# MCU.net
KiCad netlist of a schematic drawn in Altium Designer
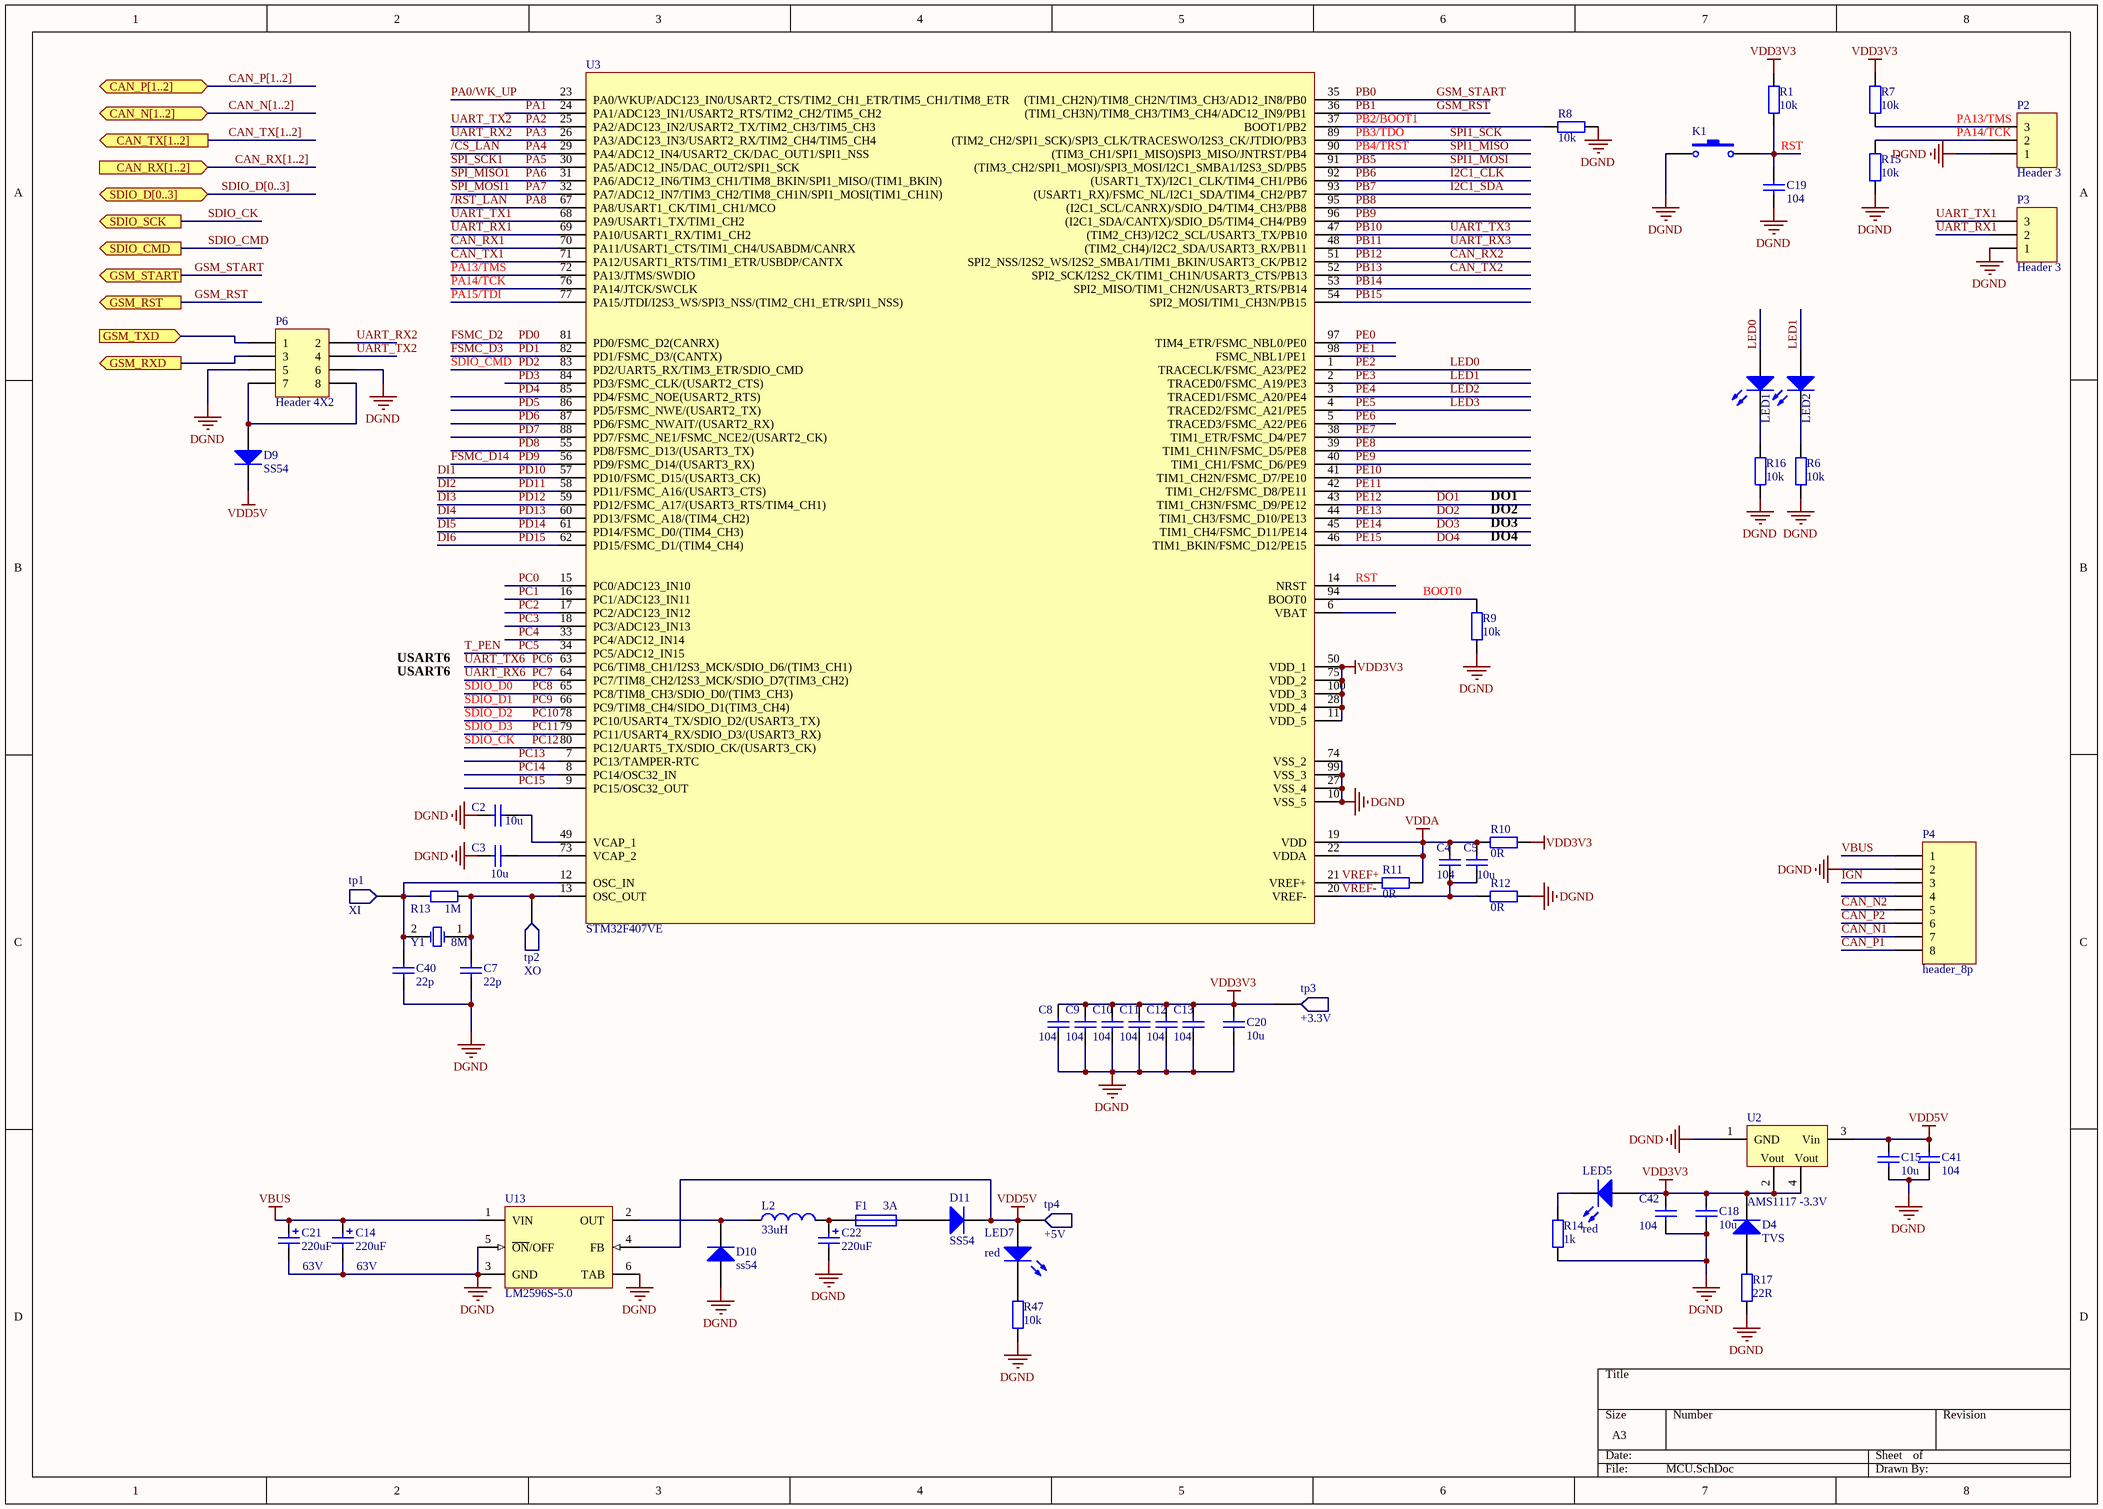
[diagram p0: MCU.SchDoc]

(export (version "E")
  (design (tool "Eeschema 10.0.6"))
  (components
    (comp (ref "C2") (value "10u") (footprint "0603_") (libsource (lib "chxxlib") (part "cap")))
    (comp (ref "C3") (value "10u") (footprint "0603_") (libsource (lib "chxxlib") (part "cap")))
    (comp (ref "C4") (value "104") (footprint "0603_") (libsource (lib "chxxlib") (part "cap")))
    (comp (ref "C5") (value "10u") (footprint "0603_") (libsource (lib "chxxlib") (part "cap")))
    (comp (ref "C7") (value "22p") (footprint "0603_") (libsource (lib "chxxlib") (part "cap")))
    (comp (ref "C8") (value "104") (footprint "0603_") (libsource (lib "chxxlib") (part "cap")))
    (comp (ref "C9") (value "104") (footprint "0603_") (libsource (lib "chxxlib") (part "cap")))
    (comp (ref "C10") (value "104") (footprint "0603_") (libsource (lib "chxxlib") (part "cap")))
    (comp (ref "C11") (value "104") (footprint "0603_") (libsource (lib "chxxlib") (part "cap")))
    (comp (ref "C12") (value "104") (footprint "0603_") (libsource (lib "chxxlib") (part "cap")))
    (comp (ref "C13") (value "104") (footprint "0603_") (libsource (lib "chxxlib") (part "cap")))
    (comp (ref "C14")
      (value "220uF")
      (footprint "Cap - 10mmx10mm")
      (fields (field (name "VDC_") "63V"))
      (libsource (lib "chxxlib") (part "cap-pol"))
    )
    (comp (ref "C15") (value "10u") (footprint "0603_") (libsource (lib "chxxlib") (part "cap")))
    (comp (ref "C18") (value "10u") (footprint "0603_") (libsource (lib "chxxlib") (part "cap")))
    (comp (ref "C19") (value "104") (footprint "0603_") (libsource (lib "chxxlib") (part "cap")))
    (comp (ref "C20") (value "10u") (footprint "0603_") (libsource (lib "chxxlib") (part "cap")))
    (comp (ref "C21")
      (value "220uF")
      (footprint "Cap - 10mmx10mm")
      (fields (field (name "VDC_") "63V"))
      (libsource (lib "chxxlib") (part "cap-pol"))
    )
    (comp (ref "C22")
      (value "220uF")
      (footprint "Cap - 10mmx10mm")
      (libsource (lib "chxxlib") (part "cap-pol"))
    )
    (comp (ref "C40") (value "22p") (footprint "0603_") (libsource (lib "chxxlib") (part "cap")))
    (comp (ref "C41") (value "104") (footprint "0603_") (libsource (lib "chxxlib") (part "cap")))
    (comp (ref "C42") (value "104") (footprint "0603_") (libsource (lib "chxxlib") (part "cap")))
    (comp (ref "D4") (value "TVS") (footprint "SMB") (libsource (lib "chxxlib") (part "diode")))
    (comp (ref "D9") (value "SS54") (footprint "SMA") (libsource (lib "chxxlib") (part "diode")))
    (comp (ref "D10") (value "ss54") (footprint "SMA") (libsource (lib "chxxlib") (part "diode")))
    (comp (ref "D11") (value "SS54") (footprint "SMA") (libsource (lib "chxxlib") (part "diode")))
    (comp (ref "F1") (value "3A") (footprint "3216") (libsource (lib "chxxlib") (part "FUSE")))
    (comp (ref "K1") (value "k") (footprint "key-2pin") (libsource (lib "chxxlib") (part "SW")))
    (comp (ref "L2") (value "33uH") (footprint "Induct 7*7*4") (libsource (lib "chxxlib") (part "inductor")))
    (comp (ref "LED1") (value "red") (footprint "0603_diode") (libsource (lib "") (part "led_1")))
    (comp (ref "LED2") (value "red") (footprint "0603_diode") (libsource (lib "") (part "led_1")))
    (comp (ref "LED5") (value "red") (footprint "0603_diode") (libsource (lib "chxxlib") (part "led")))
    (comp (ref "LED7") (value "red") (footprint "0603_diode") (libsource (lib "chxxlib") (part "led")))
    (comp (ref "P2")
      (value "Header 3")
      (footprint "HDR1X3")
      (description "Header, 3-Pin")
      (fields (field (name "PUBLISHER") "Altium Limited"))
      (libsource (lib "Miscellaneous Connectors") (part "Header 3"))
    )
    (comp (ref "P3")
      (value "Header 3")
      (footprint "HDR1X3")
      (description "Header, 3-Pin")
      (fields (field (name "PUBLISHER") "Altium Limited"))
      (libsource (lib "Miscellaneous Connectors") (part "Header 3"))
    )
    (comp (ref "P4")
      (value "header_8p")
      (footprint "WJ2EDG5.08-8P")
      (description "Pheonix Connector")
      (libsource (lib "powerboardLib") (part "header_8p"))
    )
    (comp (ref "P6")
      (value "Header 4X2")
      (footprint "HDR2X4")
      (description "Header, 4-Pin, Dual row")
      (fields (field (name "PUBLISHER") "Altium Limited"))
      (libsource (lib "Miscellaneous Connectors") (part "Header 4X2"))
    )
    (comp (ref "R1") (value "10k") (footprint "0603_") (libsource (lib "chxxlib") (part "res")))
    (comp (ref "R6") (value "10k") (footprint "0603_") (libsource (lib "chxxlib") (part "res")))
    (comp (ref "R7") (value "10k") (footprint "0603_") (libsource (lib "chxxlib") (part "res")))
    (comp (ref "R8") (value "10k") (footprint "0603_") (libsource (lib "") (part "res_1")))
    (comp (ref "R9") (value "10k") (footprint "0603_") (libsource (lib "chxxlib") (part "res")))
    (comp (ref "R10") (value "0R") (footprint "0603_") (libsource (lib "") (part "res_1")))
    (comp (ref "R11") (value "0R") (footprint "0603_") (libsource (lib "") (part "res_1")))
    (comp (ref "R12") (value "0R") (footprint "0603_") (libsource (lib "") (part "res_1")))
    (comp (ref "R13") (value "1M") (footprint "0603_") (libsource (lib "") (part "res_2")))
    (comp (ref "R14") (value "1k") (footprint "0603_") (libsource (lib "") (part "res_3")))
    (comp (ref "R15") (value "10k") (footprint "0603_") (libsource (lib "chxxlib") (part "res")))
    (comp (ref "R16") (value "10k") (footprint "0603_") (libsource (lib "chxxlib") (part "res")))
    (comp (ref "R17") (value "22R") (footprint "0603_") (libsource (lib "") (part "res_3")))
    (comp (ref "R47") (value "10k") (footprint "0603_") (libsource (lib "chxxlib") (part "res")))
    (comp (ref "tp1") (value "XI") (footprint "testPoint_s") (libsource (lib "chxxlib") (part "pad")))
    (comp (ref "tp2") (value "XO") (footprint "testPoint_s") (libsource (lib "chxxlib") (part "pad")))
    (comp (ref "tp3") (value "+3.3V") (footprint "testPoint") (libsource (lib "chxxlib") (part "pad")))
    (comp (ref "tp4") (value "+5V") (footprint "testPoint") (libsource (lib "chxxlib") (part "pad")))
    (comp (ref "U2")
      (value "AMS1117 -3.3V")
      (footprint "SOT-223")
      (libsource (lib "chxxlib") (part "AMS1117"))
    )
    (comp (ref "U3")
      (value "STM32F407VE")
      (footprint "LQFP100-M")
      (libsource (lib "chxxlib") (part "STM32F407VE"))
    )
    (comp (ref "U13")
      (value "LM2596S-5.0")
      (footprint "TS5B_N")
      (description "SIMPLE SWITCHER Power Converter 150 KHz 3A Step-Down Voltage Regulator")
      (fields
        (field (name "PARTNUMBER") "LM2596S-3.3")
        (field (name "MANUFACTURER") "National Semiconductor")
        (field (name "PUBLISHER") "Altium Limited")
      )
      (libsource (lib "NSC Switcher") (part "LM2596S-3.3"))
    )
    (comp (ref "Y1") (value "8M") (footprint "xtal") (libsource (lib "chxxlib") (part "xtal")))
  )
  (nets
    (net (code "1") (name "/BOOT0") (class "Default")
      (node (ref "R9") (pin "1") (pinfunction "1_1") (pintype "passive"))
      (node (ref "U3") (pin "94") (pinfunction "BOOT0_94") (pintype "passive"))
    )
    (net (code "2") (name "/CAN_N1") (class "Default")
      (node (ref "P4") (pin "7") (pinfunction "7_7") (pintype "passive"))
    )
    (net (code "3") (name "/CAN_N2") (class "Default")
      (node (ref "P4") (pin "5") (pinfunction "5_5") (pintype "passive"))
    )
    (net (code "5") (name "/CAN_P1") (class "Default")
      (node (ref "P4") (pin "8") (pinfunction "8_8") (pintype "passive"))
    )
    (net (code "6") (name "/CAN_P2") (class "Default")
      (node (ref "P4") (pin "6") (pinfunction "6_6") (pintype "passive"))
    )
    (net (code "8") (name "/CAN_RX1") (class "Default")
      (node (ref "U3") (pin "70") (pinfunction "PA11/USART1_CTS/TIM1_CH4/USABDM/CANRX_70") (pintype "passive"))
    )
    (net (code "9") (name "/CAN_RX2") (class "Default")
      (node (ref "U3") (pin "51") (pinfunction "SPI2_NSS/I2S2_WS/I2S2_SMBA1/TIM1_BKIN/USART3_CK/PB12_51") (pintype "passive"))
    )
    (net (code "11") (name "/CAN_TX1") (class "Default")
      (node (ref "U3") (pin "71") (pinfunction "PA12/USART1_RTS/TIM1_ETR/USBDP/CANTX_71") (pintype "passive"))
    )
    (net (code "12") (name "/CAN_TX2") (class "Default")
      (node (ref "U3") (pin "52") (pinfunction "SPI2_SCK/I2S2_CK/TIM1_CH1N/USART3_CTS/PB13_52") (pintype "passive"))
    )
    (net (code "14") (name "/DI1") (class "Default")
      (node (ref "U3") (pin "57") (pinfunction "PD10/FSMC_D15/(USART3_CK)_57") (pintype "passive"))
    )
    (net (code "15") (name "/DI2") (class "Default")
      (node (ref "U3") (pin "58") (pinfunction "PD11/FSMC_A16/(USART3_CTS)_58") (pintype "passive"))
    )
    (net (code "16") (name "/DI3") (class "Default")
      (node (ref "U3") (pin "59") (pinfunction "PD12/FSMC_A17/(USART3_RTS/TIM4_CH1)_59") (pintype "passive"))
    )
    (net (code "17") (name "/DI4") (class "Default")
      (node (ref "U3") (pin "60") (pinfunction "PD13/FSMC_A18/(TIM4_CH2)_60") (pintype "passive"))
    )
    (net (code "18") (name "/DI5") (class "Default")
      (node (ref "U3") (pin "61") (pinfunction "PD14/FSMC_D0/(TIM4_CH3)_61") (pintype "passive"))
    )
    (net (code "19") (name "/DI6") (class "Default")
      (node (ref "U3") (pin "62") (pinfunction "PD15/FSMC_D1/(TIM4_CH4)_62") (pintype "passive"))
    )
    (net (code "20") (name "/DO1") (class "Default")
      (node (ref "U3") (pin "43") (pinfunction "TIM1_CH3N/FSMC_D9/PE12_43") (pintype "passive"))
    )
    (net (code "21") (name "/DO2") (class "Default")
      (node (ref "U3") (pin "44") (pinfunction "TIM1_CH3/FSMC_D10/PE13_44") (pintype "passive"))
    )
    (net (code "22") (name "/DO3") (class "Default")
      (node (ref "U3") (pin "45") (pinfunction "TIM1_CH4/FSMC_D11/PE14_45") (pintype "passive"))
    )
    (net (code "23") (name "/DO4") (class "Default")
      (node (ref "U3") (pin "46") (pinfunction "TIM1_BKIN/FSMC_D12/PE15_46") (pintype "passive"))
    )
    (net (code "24") (name "/FSMC_D2") (class "Default")
      (node (ref "U3") (pin "81") (pinfunction "PD0/FSMC_D2(CANRX)_81") (pintype "passive"))
    )
    (net (code "25") (name "/FSMC_D3") (class "Default")
      (node (ref "U3") (pin "82") (pinfunction "PD1/FSMC_D3/(CANTX)_82") (pintype "passive"))
    )
    (net (code "26") (name "/FSMC_D14") (class "Default")
      (node (ref "U3") (pin "56") (pinfunction "PD9/FSMC_D14/(USART3_RX)_56") (pintype "passive"))
    )
    (net (code "27") (name "/GSM_RST") (class "Default")
      (node (ref "U3") (pin "36") (pinfunction "(TIM1_CH3N)/TIM8_CH3/TIM3_CH4/ADC12_IN9/PB1_36") (pintype "passive"))
    )
    (net (code "28") (name "/GSM_RXD") (class "Default")
      (node (ref "P6") (pin "3") (pinfunction "3_3") (pintype "passive"))
    )
    (net (code "29") (name "/GSM_START") (class "Default")
      (node (ref "U3") (pin "35") (pinfunction "(TIM1_CH2N)/TIM8_CH2N/TIM3_CH3/AD12_IN8/PB0_35") (pintype "passive"))
    )
    (net (code "30") (name "/GSM_TXD") (class "Default")
      (node (ref "P6") (pin "1") (pinfunction "1_1") (pintype "passive"))
    )
    (net (code "31") (name "/I2C1_CLK") (class "Default")
      (node (ref "U3") (pin "92") (pinfunction "(USART1_TX)/I2C1_CLK/TIM4_CH1/PB6_92") (pintype "passive"))
    )
    (net (code "32") (name "/I2C1_SDA") (class "Default")
      (node (ref "U3") (pin "93") (pinfunction "(USART1_RX)/FSMC_NL/I2C1_SDA/TIM4_CH2/PB7_93") (pintype "passive"))
    )
    (net (code "33") (name "/IGN") (class "Default")
      (node (ref "P4") (pin "3") (pinfunction "3_3") (pintype "passive"))
    )
    (net (code "34") (name "/LED0") (class "Default")
      (node (ref "LED1") (pin "1") (pinfunction "A_1") (pintype "passive"))
      (node (ref "U3") (pin "1") (pinfunction "TRACECLK/FSMC_A23/PE2_1") (pintype "passive"))
    )
    (net (code "35") (name "/LED1") (class "Default")
      (node (ref "LED2") (pin "1") (pinfunction "A_1") (pintype "passive"))
      (node (ref "U3") (pin "2") (pinfunction "TRACED0/FSMC_A19/PE3_2") (pintype "passive"))
    )
    (net (code "36") (name "/LED2") (class "Default")
      (node (ref "U3") (pin "3") (pinfunction "TRACED1/FSMC_A20/PE4_3") (pintype "passive"))
    )
    (net (code "37") (name "/LED3") (class "Default")
      (node (ref "U3") (pin "4") (pinfunction "TRACED2/FSMC_A21/PE5_4") (pintype "passive"))
    )
    (net (code "38") (name "/PA0{slash}WK_UP") (class "Default")
      (node (ref "U3") (pin "23") (pinfunction "PA0/WKUP/ADC123_IN0/USART2_CTS/TIM2_CH1_ETR/TIM5_CH1/TIM8_ETR_23") (pintype "passive"))
    )
    (net (code "39") (name "/PA1") (class "Default")
      (node (ref "U3") (pin "24") (pinfunction "PA1/ADC123_IN1/USART2_RTS/TIM2_CH2/TIM5_CH2_24") (pintype "passive"))
    )
    (net (code "40") (name "/PA2") (class "Default")
      (node (ref "P6") (pin "4") (pinfunction "4_4") (pintype "passive"))
      (node (ref "U3") (pin "25") (pinfunction "PA2/ADC123_IN2/USART2_TX/TIM2_CH3/TIM5_CH3_25") (pintype "passive"))
    )
    (net (code "41") (name "/PA3") (class "Default")
      (node (ref "P6") (pin "2") (pinfunction "2_2") (pintype "passive"))
      (node (ref "U3") (pin "26") (pinfunction "PA3/ADC123_IN3/USART2_RX/TIM2_CH4/TIM5_CH4_26") (pintype "passive"))
    )
    (net (code "42") (name "/PA4") (class "Default")
      (node (ref "U3") (pin "29") (pinfunction "PA4/ADC12_IN4/USART2_CK/DAC_OUT1/SPI1_NSS_29") (pintype "passive"))
    )
    (net (code "43") (name "/PA5") (class "Default")
      (node (ref "U3") (pin "30") (pinfunction "PA5/ADC12_IN5/DAC_OUT2/SPI1_SCK_30") (pintype "passive"))
    )
    (net (code "44") (name "/PA6") (class "Default")
      (node (ref "U3") (pin "31") (pinfunction "PA6/ADC12_IN6/TIM3_CH1/TIM8_BKIN/SPI1_MISO/(TIM1_BKIN)_31") (pintype "passive"))
    )
    (net (code "45") (name "/PA7") (class "Default")
      (node (ref "U3") (pin "32") (pinfunction "PA7/ADC12_IN7/TIM3_CH2/TIM8_CH1N/SPI1_MOSI(TIM1_CH1N)_32") (pintype "passive"))
    )
    (net (code "46") (name "/PA8") (class "Default")
      (node (ref "U3") (pin "67") (pinfunction "PA8/USART1_CK/TIM1_CH1/MCO_67") (pintype "passive"))
    )
    (net (code "47") (name "/PA13{slash}TMS") (class "Default")
      (node (ref "P2") (pin "3") (pinfunction "3_3") (pintype "passive"))
      (node (ref "R7") (pin "2") (pinfunction "2_2") (pintype "passive"))
      (node (ref "U3") (pin "72") (pinfunction "PA13/JTMS/SWDIO_72") (pintype "passive"))
    )
    (net (code "48") (name "/PA14{slash}TCK") (class "Default")
      (node (ref "P2") (pin "2") (pinfunction "2_2") (pintype "passive"))
      (node (ref "R15") (pin "1") (pinfunction "1_1") (pintype "passive"))
      (node (ref "U3") (pin "76") (pinfunction "PA14/JTCK/SWCLK_76") (pintype "passive"))
    )
    (net (code "49") (name "/PA15{slash}TDI") (class "Default")
      (node (ref "U3") (pin "77") (pinfunction "PA15/JTDI/I2S3_WS/SPI3_NSS/(TIM2_CH1_ETR/SPI1_NSS)_77") (pintype "passive"))
    )
    (net (code "50") (name "/PB2{slash}BOOT1") (class "Default")
      (node (ref "R8") (pin "1") (pinfunction "1_1") (pintype "passive"))
      (node (ref "U3") (pin "37") (pinfunction "BOOT1/PB2_37") (pintype "passive"))
    )
    (net (code "51") (name "/PB3{slash}TDO") (class "Default")
      (node (ref "U3") (pin "89") (pinfunction "(TIM2_CH2/SPI1_SCK)/SPI3_CLK/TRACESWO/I2S3_CK/JTDIO/PB3_89") (pintype "passive"))
    )
    (net (code "52") (name "/PB4{slash}TRST") (class "Default")
      (node (ref "U3") (pin "90") (pinfunction "(TIM3_CH1/SPI1_MISO)SPI3_MISO/JNTRST/PB4_90") (pintype "passive"))
    )
    (net (code "53") (name "/PB5") (class "Default")
      (node (ref "U3") (pin "91") (pinfunction "(TIM3_CH2/SPI1_MOSI)/SPI3_MOSI/I2C1_SMBA1/I2S3_SD/PB5_91") (pintype "passive"))
    )
    (net (code "54") (name "/PB8") (class "Default")
      (node (ref "U3") (pin "95") (pinfunction "(I2C1_SCL/CANRX)/SDIO_D4/TIM4_CH3/PB8_95") (pintype "passive"))
    )
    (net (code "55") (name "/PB9") (class "Default")
      (node (ref "U3") (pin "96") (pinfunction "(I2C1_SDA/CANTX)/SDIO_D5/TIM4_CH4/PB9_96") (pintype "passive"))
    )
    (net (code "56") (name "/PB10") (class "Default")
      (node (ref "U3") (pin "47") (pinfunction "(TIM2_CH3)/I2C2_SCL/USART3_TX/PB10_47") (pintype "passive"))
    )
    (net (code "57") (name "/PB11") (class "Default")
      (node (ref "U3") (pin "48") (pinfunction "(TIM2_CH4)/I2C2_SDA/USART3_RX/PB11_48") (pintype "passive"))
    )
    (net (code "58") (name "/PB14") (class "Default")
      (node (ref "U3") (pin "53") (pinfunction "SPI2_MISO/TIM1_CH2N/USART3_RTS/PB14_53") (pintype "passive"))
    )
    (net (code "59") (name "/PB15") (class "Default")
      (node (ref "U3") (pin "54") (pinfunction "SPI2_MOSI/TIM1_CH3N/PB15_54") (pintype "passive"))
    )
    (net (code "60") (name "/PC0") (class "Default")
      (node (ref "U3") (pin "15") (pinfunction "PC0/ADC123_IN10_15") (pintype "passive"))
    )
    (net (code "61") (name "/PC1") (class "Default")
      (node (ref "U3") (pin "16") (pinfunction "PC1/ADC123_IN11_16") (pintype "passive"))
    )
    (net (code "62") (name "/PC2") (class "Default")
      (node (ref "U3") (pin "17") (pinfunction "PC2/ADC123_IN12_17") (pintype "passive"))
    )
    (net (code "63") (name "/PC3") (class "Default")
      (node (ref "U3") (pin "18") (pinfunction "PC3/ADC123_IN13_18") (pintype "passive"))
    )
    (net (code "64") (name "/PC4") (class "Default")
      (node (ref "U3") (pin "33") (pinfunction "PC4/ADC12_IN14_33") (pintype "passive"))
    )
    (net (code "65") (name "/PC5") (class "Default")
      (node (ref "U3") (pin "34") (pinfunction "PC5/ADC12_IN15_34") (pintype "passive"))
    )
    (net (code "66") (name "/PC6") (class "Default")
      (node (ref "U3") (pin "63") (pinfunction "PC6/TIM8_CH1/I2S3_MCK/SDIO_D6/(TIM3_CH1)_63") (pintype "passive"))
    )
    (net (code "67") (name "/PC7") (class "Default")
      (node (ref "U3") (pin "64") (pinfunction "PC7/TIM8_CH2/I2S3_MCK/SDIO_D7(TIM3_CH2)_64") (pintype "passive"))
    )
    (net (code "68") (name "/PC12") (class "Default")
      (node (ref "U3") (pin "80") (pinfunction "PC12/UART5_TX/SDIO_CK/(USART3_CK)_80") (pintype "passive"))
    )
    (net (code "69") (name "/PC13") (class "Default")
      (node (ref "U3") (pin "7") (pinfunction "PC13/TAMPER-RTC_7") (pintype "passive"))
    )
    (net (code "70") (name "/PC14") (class "Default")
      (node (ref "U3") (pin "8") (pinfunction "PC14/OSC32_IN_8") (pintype "passive"))
    )
    (net (code "71") (name "/PC15") (class "Default")
      (node (ref "U3") (pin "9") (pinfunction "PC15/OSC32_OUT_9") (pintype "passive"))
    )
    (net (code "72") (name "/PD2") (class "Default")
      (node (ref "U3") (pin "83") (pinfunction "PD2/UART5_RX/TIM3_ETR/SDIO_CMD_83") (pintype "passive"))
    )
    (net (code "73") (name "/PD3") (class "Default")
      (node (ref "U3") (pin "84") (pinfunction "PD3/FSMC_CLK/(USART2_CTS)_84") (pintype "passive"))
    )
    (net (code "74") (name "/PD4") (class "Default")
      (node (ref "U3") (pin "85") (pinfunction "PD4/FSMC_NOE(USART2_RTS)_85") (pintype "passive"))
    )
    (net (code "75") (name "/PD5") (class "Default")
      (node (ref "U3") (pin "86") (pinfunction "PD5/FSMC_NWE/(USART2_TX)_86") (pintype "passive"))
    )
    (net (code "76") (name "/PD6") (class "Default")
      (node (ref "U3") (pin "87") (pinfunction "PD6/FSMC_NWAIT/(USART2_RX)_87") (pintype "passive"))
    )
    (net (code "77") (name "/PD7") (class "Default")
      (node (ref "U3") (pin "88") (pinfunction "PD7/FSMC_NE1/FSMC_NCE2/(USART2_CK)_88") (pintype "passive"))
    )
    (net (code "78") (name "/PD8") (class "Default")
      (node (ref "U3") (pin "55") (pinfunction "PD8/FSMC_D13/(USART3_TX)_55") (pintype "passive"))
    )
    (net (code "79") (name "/PE0") (class "Default")
      (node (ref "U3") (pin "97") (pinfunction "TIM4_ETR/FSMC_NBL0/PE0_97") (pintype "passive"))
    )
    (net (code "80") (name "/PE1") (class "Default")
      (node (ref "U3") (pin "98") (pinfunction "FSMC_NBL1/PE1_98") (pintype "passive"))
    )
    (net (code "81") (name "/PE6") (class "Default")
      (node (ref "U3") (pin "5") (pinfunction "TRACED3/FSMC_A22/PE6_5") (pintype "passive"))
    )
    (net (code "82") (name "/PE7") (class "Default")
      (node (ref "U3") (pin "38") (pinfunction "TIM1_ETR/FSMC_D4/PE7_38") (pintype "passive"))
    )
    (net (code "83") (name "/PE8") (class "Default")
      (node (ref "U3") (pin "39") (pinfunction "TIM1_CH1N/FSMC_D5/PE8_39") (pintype "passive"))
    )
    (net (code "84") (name "/PE9") (class "Default")
      (node (ref "U3") (pin "40") (pinfunction "TIM1_CH1/FSMC_D6/PE9_40") (pintype "passive"))
    )
    (net (code "85") (name "/PE10") (class "Default")
      (node (ref "U3") (pin "41") (pinfunction "TIM1_CH2N/FSMC_D7/PE10_41") (pintype "passive"))
    )
    (net (code "86") (name "/PE11") (class "Default")
      (node (ref "U3") (pin "42") (pinfunction "TIM1_CH2/FSMC_D8/PE11_42") (pintype "passive"))
    )
    (net (code "87") (name "/RST") (class "Default")
      (node (ref "C19") (pin "1") (pinfunction "1_1") (pintype "passive"))
      (node (ref "K1") (pin "2") (pinfunction "2_2") (pintype "passive"))
      (node (ref "R1") (pin "2") (pinfunction "2_2") (pintype "passive"))
      (node (ref "U3") (pin "14") (pinfunction "NRST_14") (pintype "passive"))
    )
    (net (code "88") (name "/SDIO_D0") (class "Default")
      (node (ref "U3") (pin "65") (pinfunction "PC8/TIM8_CH3/SDIO_D0/(TIM3_CH3)_65") (pintype "passive"))
    )
    (net (code "89") (name "/SDIO_D1") (class "Default")
      (node (ref "U3") (pin "66") (pinfunction "PC9/TIM8_CH4/SIDO_D1(TIM3_CH4)_66") (pintype "passive"))
    )
    (net (code "90") (name "/SDIO_D2") (class "Default")
      (node (ref "U3") (pin "78") (pinfunction "PC10/USART4_TX/SDIO_D2/(USART3_TX)_78") (pintype "passive"))
    )
    (net (code "91") (name "/SDIO_D3") (class "Default")
      (node (ref "U3") (pin "79") (pinfunction "PC11/USART4_RX/SDIO_D3/(USART3_RX)_79") (pintype "passive"))
    )
    (net (code "93") (name "/UART_RX1") (class "Default")
      (node (ref "P3") (pin "2") (pinfunction "2_2") (pintype "passive"))
      (node (ref "U3") (pin "69") (pinfunction "PA10/USART1_RX/TIM1_CH2_69") (pintype "passive"))
    )
    (net (code "94") (name "/UART_TX1") (class "Default")
      (node (ref "P3") (pin "3") (pinfunction "3_3") (pintype "passive"))
      (node (ref "U3") (pin "68") (pinfunction "PA9/USART1_TX/TIM1_CH2_68") (pintype "passive"))
    )
    (net (code "95") (name "/VREF+") (class "Default")
      (node (ref "R11") (pin "1") (pinfunction "1_1") (pintype "passive"))
      (node (ref "U3") (pin "21") (pinfunction "VREF+_21") (pintype "passive"))
    )
    (net (code "96") (name "/VREF-") (class "Default")
      (node (ref "C4") (pin "2") (pinfunction "2_2") (pintype "passive"))
      (node (ref "C5") (pin "2") (pinfunction "2_2") (pintype "passive"))
      (node (ref "R12") (pin "1") (pinfunction "1_1") (pintype "passive"))
      (node (ref "U3") (pin "20") (pinfunction "VREF-_20") (pintype "passive"))
    )
    (net (code "97") (name "DGND") (class "Default")
      (node (ref "C10") (pin "2") (pinfunction "2_2") (pintype "passive"))
      (node (ref "C11") (pin "2") (pinfunction "2_2") (pintype "passive"))
      (node (ref "C12") (pin "2") (pinfunction "2_2") (pintype "passive"))
      (node (ref "C13") (pin "2") (pinfunction "2_2") (pintype "passive"))
      (node (ref "C14") (pin "2") (pinfunction "2_2") (pintype "passive"))
      (node (ref "C15") (pin "1") (pinfunction "1_1") (pintype "passive"))
      (node (ref "C18") (pin "1") (pinfunction "1_1") (pintype "passive"))
      (node (ref "C19") (pin "2") (pinfunction "2_2") (pintype "passive"))
      (node (ref "C2") (pin "1") (pinfunction "1_1") (pintype "passive"))
      (node (ref "C20") (pin "1") (pinfunction "1_1") (pintype "passive"))
      (node (ref "C21") (pin "2") (pinfunction "2_2") (pintype "passive"))
      (node (ref "C22") (pin "2") (pinfunction "2_2") (pintype "passive"))
      (node (ref "C3") (pin "1") (pinfunction "1_1") (pintype "passive"))
      (node (ref "C40") (pin "1") (pinfunction "1_1") (pintype "passive"))
      (node (ref "C41") (pin "2") (pinfunction "2_2") (pintype "passive"))
      (node (ref "C42") (pin "2") (pinfunction "2_2") (pintype "passive"))
      (node (ref "C7") (pin "1") (pinfunction "1_1") (pintype "passive"))
      (node (ref "C8") (pin "2") (pinfunction "2_2") (pintype "passive"))
      (node (ref "C9") (pin "2") (pinfunction "2_2") (pintype "passive"))
      (node (ref "D10") (pin "A") (pinfunction "A_A") (pintype "passive"))
      (node (ref "K1") (pin "1") (pinfunction "1_1") (pintype "passive"))
      (node (ref "P2") (pin "1") (pinfunction "1_1") (pintype "passive"))
      (node (ref "P3") (pin "1") (pinfunction "1_1") (pintype "passive"))
      (node (ref "P4") (pin "2") (pinfunction "2_2") (pintype "passive"))
      (node (ref "P6") (pin "5") (pinfunction "5_5") (pintype "passive"))
      (node (ref "P6") (pin "6") (pinfunction "6_6") (pintype "passive"))
      (node (ref "R12") (pin "2") (pinfunction "2_2") (pintype "passive"))
      (node (ref "R14") (pin "1") (pinfunction "1_1") (pintype "passive"))
      (node (ref "R15") (pin "2") (pinfunction "2_2") (pintype "passive"))
      (node (ref "R16") (pin "2") (pinfunction "2_2") (pintype "passive"))
      (node (ref "R17") (pin "1") (pinfunction "1_1") (pintype "passive"))
      (node (ref "R47") (pin "2") (pinfunction "2_2") (pintype "passive"))
      (node (ref "R6") (pin "2") (pinfunction "2_2") (pintype "passive"))
      (node (ref "R8") (pin "2") (pinfunction "2_2") (pintype "passive"))
      (node (ref "R9") (pin "2") (pinfunction "2_2") (pintype "passive"))
      (node (ref "U13") (pin "3") (pinfunction "GND_3") (pintype "power_in"))
      (node (ref "U13") (pin "5") (pinfunction "~{ON}/OFF_5") (pintype "input"))
      (node (ref "U13") (pin "6") (pinfunction "TAB_6") (pintype "power_in"))
      (node (ref "U2") (pin "1") (pinfunction "GND_1") (pintype "passive"))
      (node (ref "U3") (pin "10") (pinfunction "VSS_5_10") (pintype "passive"))
      (node (ref "U3") (pin "27") (pinfunction "VSS_4_27") (pintype "passive"))
      (node (ref "U3") (pin "74") (pinfunction "VSS_2_74") (pintype "passive"))
      (node (ref "U3") (pin "99") (pinfunction "VSS_3_99") (pintype "passive"))
    )
    (net (code "98") (name "Net-(C22-Pad1)") (class "Default")
      (node (ref "C22") (pin "1") (pinfunction "1_1") (pintype "passive"))
      (node (ref "F1") (pin "1") (pinfunction "1_1") (pintype "passive"))
      (node (ref "L2") (pin "2") (pinfunction "2_2") (pintype "passive"))
    )
    (net (code "99") (name "Net-(D4-PadA)") (class "Default")
      (node (ref "D4") (pin "A") (pinfunction "A_A") (pintype "passive"))
      (node (ref "R17") (pin "2") (pinfunction "2_2") (pintype "passive"))
    )
    (net (code "100") (name "Net-(D9-PadA)") (class "Default")
      (node (ref "D9") (pin "A") (pinfunction "A_A") (pintype "passive"))
      (node (ref "P6") (pin "7") (pinfunction "7_7") (pintype "passive"))
      (node (ref "P6") (pin "8") (pinfunction "8_8") (pintype "passive"))
    )
    (net (code "101") (name "Net-(D11-PadA)") (class "Default")
      (node (ref "D11") (pin "A") (pinfunction "A_A") (pintype "passive"))
      (node (ref "F1") (pin "2") (pinfunction "2_2") (pintype "passive"))
    )
    (net (code "102") (name "Net-(LED1-K)") (class "Default")
      (node (ref "LED1") (pin "2") (pinfunction "K_2") (pintype "passive"))
      (node (ref "R16") (pin "1") (pinfunction "1_1") (pintype "passive"))
    )
    (net (code "103") (name "Net-(LED2-K)") (class "Default")
      (node (ref "LED2") (pin "2") (pinfunction "K_2") (pintype "passive"))
      (node (ref "R6") (pin "1") (pinfunction "1_1") (pintype "passive"))
    )
    (net (code "104") (name "Net-(LED5-K)") (class "Default")
      (node (ref "LED5") (pin "2") (pinfunction "K_2") (pintype "passive"))
      (node (ref "R14") (pin "2") (pinfunction "2_2") (pintype "passive"))
    )
    (net (code "105") (name "Net-(LED7-K)") (class "Default")
      (node (ref "LED7") (pin "2") (pinfunction "K_2") (pintype "passive"))
      (node (ref "R47") (pin "1") (pinfunction "1_1") (pintype "passive"))
    )
    (net (code "106") (name "Net-(U3-OSC_IN)") (class "Default")
      (node (ref "C40") (pin "2") (pinfunction "2_2") (pintype "passive"))
      (node (ref "R13") (pin "2") (pinfunction "2_2") (pintype "passive"))
      (node (ref "U3") (pin "12") (pinfunction "OSC_IN_12") (pintype "passive"))
      (node (ref "Y1") (pin "2") (pinfunction "OSC2_2") (pintype "passive"))
      (node (ref "tp1") (pin "1") (pinfunction "1_1") (pintype "power_in"))
    )
    (net (code "107") (name "Net-(U3-OSC_OUT)") (class "Default")
      (node (ref "C7") (pin "2") (pinfunction "2_2") (pintype "passive"))
      (node (ref "R13") (pin "1") (pinfunction "1_1") (pintype "passive"))
      (node (ref "U3") (pin "13") (pinfunction "OSC_OUT_13") (pintype "passive"))
      (node (ref "Y1") (pin "1") (pinfunction "OSC1_1") (pintype "passive"))
      (node (ref "tp2") (pin "1") (pinfunction "1_1") (pintype "power_in"))
    )
    (net (code "108") (name "Net-(U3-VCAP_1)") (class "Default")
      (node (ref "C2") (pin "2") (pinfunction "2_2") (pintype "passive"))
      (node (ref "U3") (pin "49") (pinfunction "VCAP_1_49") (pintype "passive"))
    )
    (net (code "109") (name "Net-(U3-VCAP_2)") (class "Default")
      (node (ref "C3") (pin "2") (pinfunction "2_2") (pintype "passive"))
      (node (ref "U3") (pin "73") (pinfunction "VCAP_2_73") (pintype "passive"))
    )
    (net (code "110") (name "Net-(U13-OUT)") (class "Default")
      (node (ref "D10") (pin "K") (pinfunction "K_K") (pintype "passive"))
      (node (ref "L2") (pin "1") (pinfunction "1_1") (pintype "passive"))
      (node (ref "U13") (pin "2") (pinfunction "OUT_2") (pintype "power_in"))
    )
    (net (code "111") (name "VBUS") (class "Default")
      (node (ref "C14") (pin "1") (pinfunction "1_1") (pintype "passive"))
      (node (ref "C21") (pin "1") (pinfunction "1_1") (pintype "passive"))
      (node (ref "P4") (pin "1") (pinfunction "1_1") (pintype "passive"))
      (node (ref "U13") (pin "1") (pinfunction "VIN_1") (pintype "power_in"))
    )
    (net (code "112") (name "VDD3V3") (class "Default")
      (node (ref "C10") (pin "1") (pinfunction "1_1") (pintype "passive"))
      (node (ref "C11") (pin "1") (pinfunction "1_1") (pintype "passive"))
      (node (ref "C12") (pin "1") (pinfunction "1_1") (pintype "passive"))
      (node (ref "C13") (pin "1") (pinfunction "1_1") (pintype "passive"))
      (node (ref "C18") (pin "2") (pinfunction "2_2") (pintype "passive"))
      (node (ref "C20") (pin "2") (pinfunction "2_2") (pintype "passive"))
      (node (ref "C42") (pin "1") (pinfunction "1_1") (pintype "passive"))
      (node (ref "C8") (pin "1") (pinfunction "1_1") (pintype "passive"))
      (node (ref "C9") (pin "1") (pinfunction "1_1") (pintype "passive"))
      (node (ref "D4") (pin "K") (pinfunction "K_K") (pintype "passive"))
      (node (ref "LED5") (pin "1") (pinfunction "A_1") (pintype "passive"))
      (node (ref "R1") (pin "1") (pinfunction "1_1") (pintype "passive"))
      (node (ref "R10") (pin "2") (pinfunction "2_2") (pintype "passive"))
      (node (ref "R7") (pin "1") (pinfunction "1_1") (pintype "passive"))
      (node (ref "U2") (pin "2") (pinfunction "Vout_2") (pintype "passive"))
      (node (ref "U2") (pin "4") (pinfunction "Vout_4") (pintype "passive"))
      (node (ref "U3") (pin "100") (pinfunction "VDD_3_100") (pintype "passive"))
      (node (ref "U3") (pin "11") (pinfunction "VDD_5_11") (pintype "passive"))
      (node (ref "U3") (pin "28") (pinfunction "VDD_4_28") (pintype "passive"))
      (node (ref "U3") (pin "50") (pinfunction "VDD_1_50") (pintype "passive"))
      (node (ref "U3") (pin "75") (pinfunction "VDD_2_75") (pintype "passive"))
      (node (ref "tp3") (pin "1") (pinfunction "1_1") (pintype "power_in"))
    )
    (net (code "113") (name "VDD5V") (class "Default")
      (node (ref "C15") (pin "2") (pinfunction "2_2") (pintype "passive"))
      (node (ref "C41") (pin "1") (pinfunction "1_1") (pintype "passive"))
      (node (ref "D11") (pin "K") (pinfunction "K_K") (pintype "passive"))
      (node (ref "D9") (pin "K") (pinfunction "K_K") (pintype "passive"))
      (node (ref "LED7") (pin "1") (pinfunction "A_1") (pintype "passive"))
      (node (ref "U13") (pin "4") (pinfunction "FB_4") (pintype "input"))
      (node (ref "U2") (pin "3") (pinfunction "Vin_3") (pintype "passive"))
      (node (ref "tp4") (pin "1") (pinfunction "1_1") (pintype "power_in"))
    )
    (net (code "114") (name "VDDA") (class "Default")
      (node (ref "C4") (pin "1") (pinfunction "1_1") (pintype "passive"))
      (node (ref "C5") (pin "1") (pinfunction "1_1") (pintype "passive"))
      (node (ref "R10") (pin "1") (pinfunction "1_1") (pintype "passive"))
      (node (ref "R11") (pin "2") (pinfunction "2_2") (pintype "passive"))
      (node (ref "U3") (pin "19") (pinfunction "VDD_19") (pintype "passive"))
      (node (ref "U3") (pin "22") (pinfunction "VDDA_22") (pintype "passive"))
    )
    (net (code "115") (name "unconnected-(P4-Pad4)") (class "Default")
      (node (ref "P4") (pin "4") (pinfunction "4_4") (pintype "passive"))
    )
    (net (code "116") (name "unconnected-(U3-VBAT-Pad6)") (class "Default")
      (node (ref "U3") (pin "6") (pinfunction "VBAT_6") (pintype "passive"))
    )
  )
)
